# pot_controller_v1_0.net
KiCad netlist of a schematic drawn in EAGLE
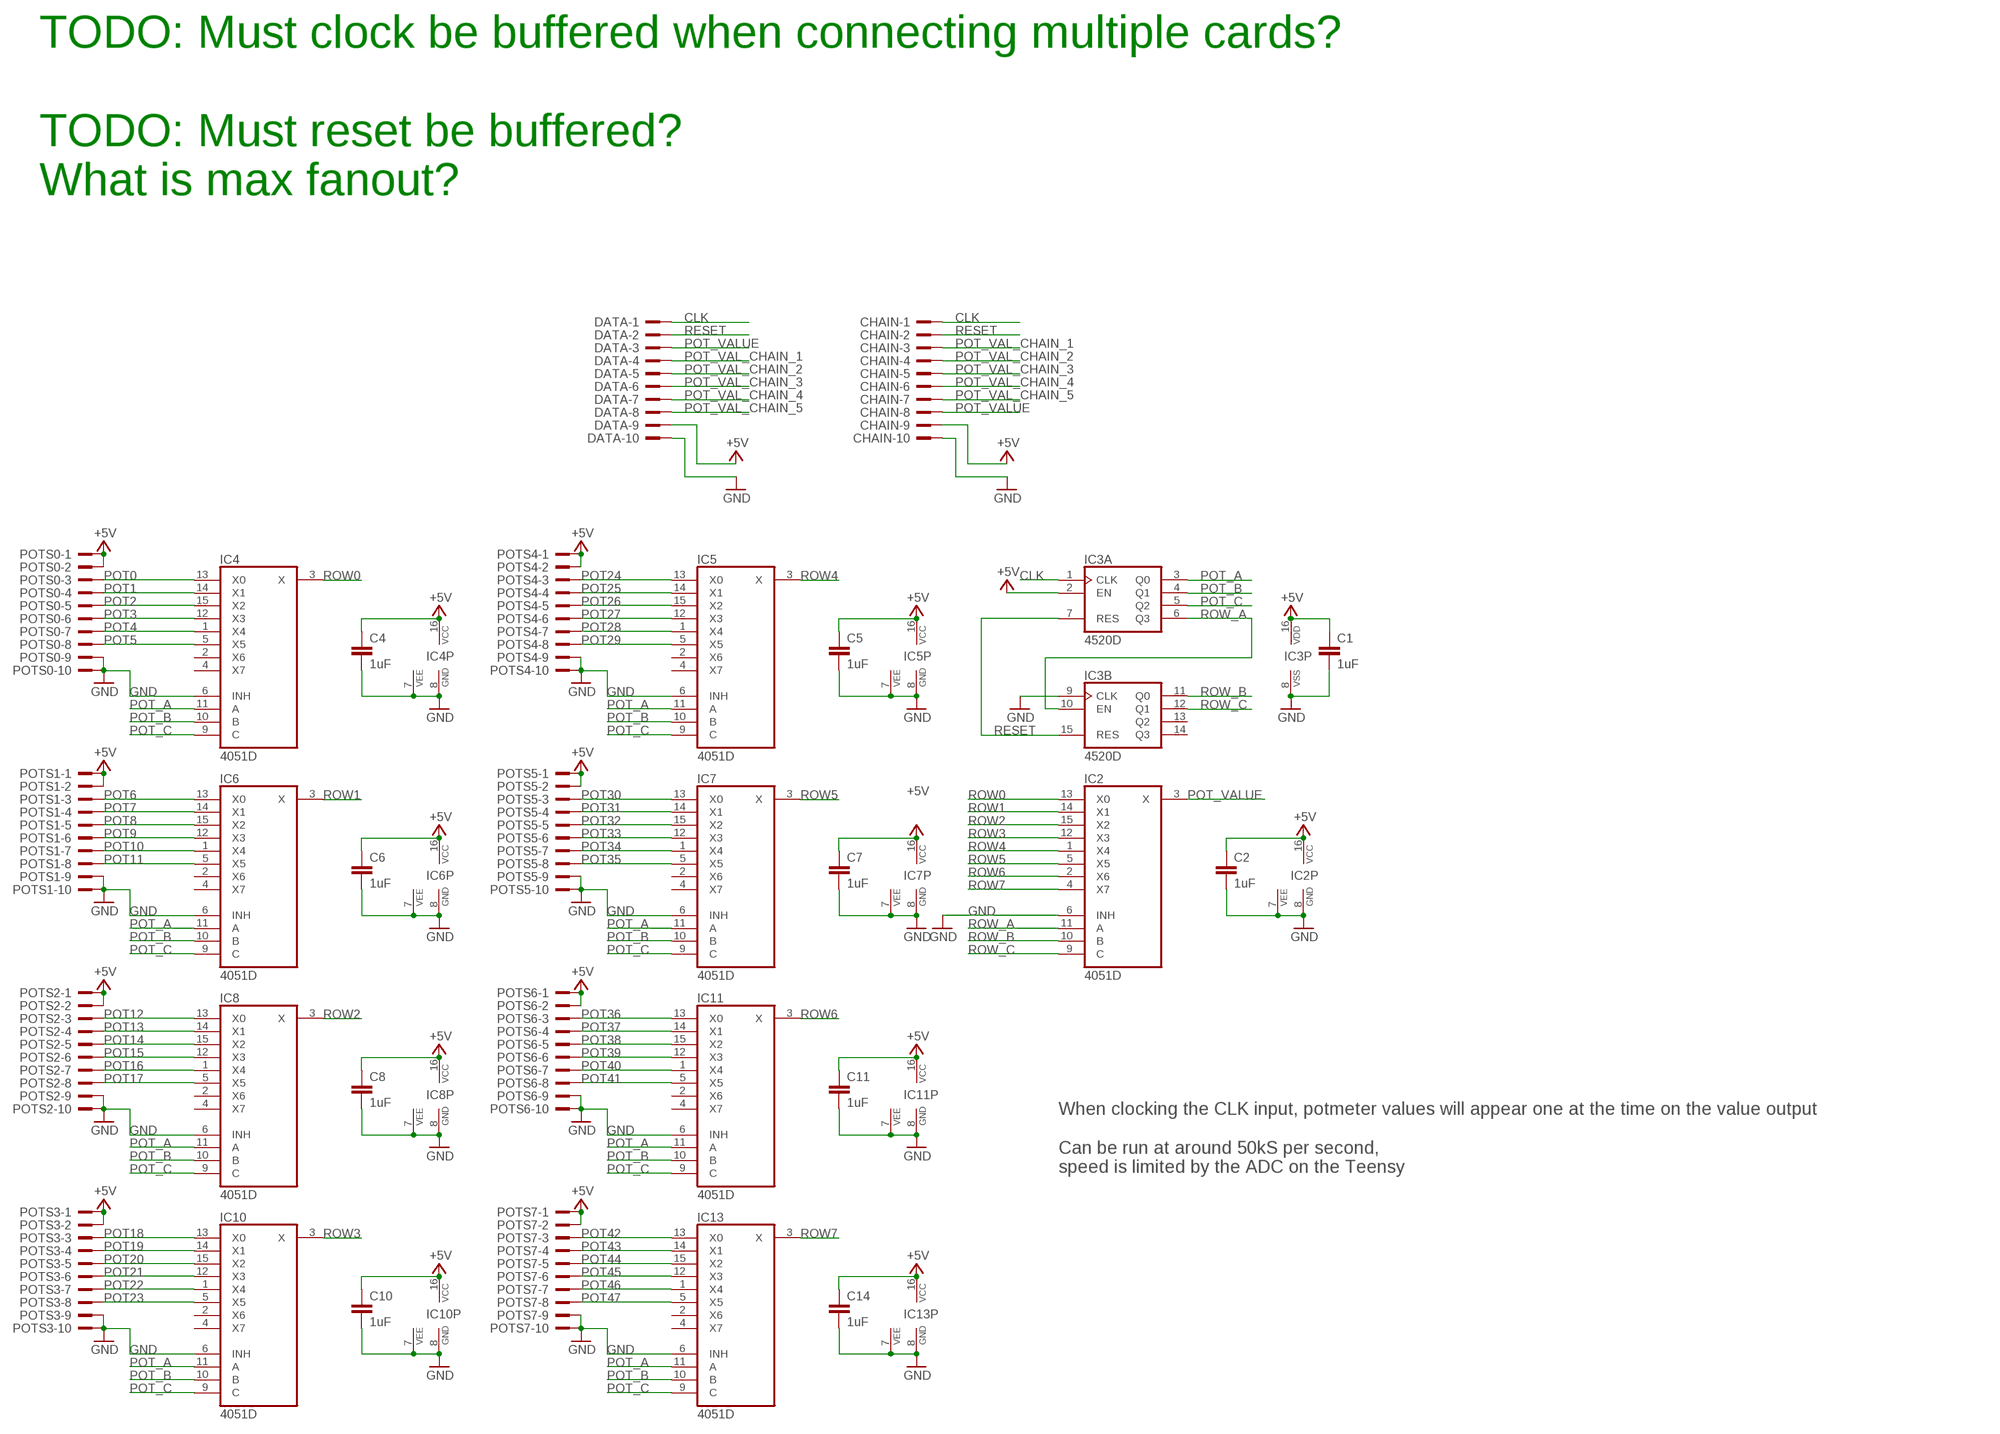
[diagram p0: schematic, sheet 1]

(export (version "E")
  (design (tool "Eeschema 10.0.6"))
  (components
    (comp (ref "C1")
      (value "1uF")
      (footprint "eagle-import:C0603-J")
      (libsource (lib "eagle-import") (part "C-EU-J0603"))
    )
    (comp (ref "C2")
      (value "1uF")
      (footprint "eagle-import:C0603-J")
      (libsource (lib "eagle-import") (part "C-EU-J0603"))
    )
    (comp (ref "C4")
      (value "1uF")
      (footprint "eagle-import:C0603-J")
      (libsource (lib "eagle-import") (part "C-EU-J0603"))
    )
    (comp (ref "C5")
      (value "1uF")
      (footprint "eagle-import:C0603-J")
      (libsource (lib "eagle-import") (part "C-EU-J0603"))
    )
    (comp (ref "C6")
      (value "1uF")
      (footprint "eagle-import:C0603-J")
      (libsource (lib "eagle-import") (part "C-EU-J0603"))
    )
    (comp (ref "C7")
      (value "1uF")
      (footprint "eagle-import:C0603-J")
      (libsource (lib "eagle-import") (part "C-EU-J0603"))
    )
    (comp (ref "C8")
      (value "1uF")
      (footprint "eagle-import:C0603-J")
      (libsource (lib "eagle-import") (part "C-EU-J0603"))
    )
    (comp (ref "C10")
      (value "1uF")
      (footprint "eagle-import:C0603-J")
      (libsource (lib "eagle-import") (part "C-EU-J0603"))
    )
    (comp (ref "C11")
      (value "1uF")
      (footprint "eagle-import:C0603-J")
      (libsource (lib "eagle-import") (part "C-EU-J0603"))
    )
    (comp (ref "C14")
      (value "1uF")
      (footprint "eagle-import:C0603-J")
      (libsource (lib "eagle-import") (part "C-EU-J0603"))
    )
    (comp (ref "CHAIN")
      (value "CONN-IDC-10PS")
      (footprint "eagle-import:CONN-IDC10P-S")
      (libsource (lib "eagle-import") (part "CONN-IDC-10PS"))
    )
    (comp (ref "DATA")
      (value "CONN-IDC-10PS")
      (footprint "eagle-import:CONN-IDC10P-S")
      (libsource (lib "eagle-import") (part "CONN-IDC-10PS"))
    )
    (comp (ref "IC2")
      (value "4051D")
      (footprint "eagle-import:SO16")
      (libsource (lib "eagle-import") (part "4051D"))
    )
    (comp (ref "IC3")
      (value "4520D")
      (footprint "eagle-import:SO16")
      (libsource (lib "eagle-import") (part "4520D"))
    )
    (comp (ref "IC4")
      (value "4051D")
      (footprint "eagle-import:SO16")
      (libsource (lib "eagle-import") (part "4051D"))
    )
    (comp (ref "IC5")
      (value "4051D")
      (footprint "eagle-import:SO16")
      (libsource (lib "eagle-import") (part "4051D"))
    )
    (comp (ref "IC6")
      (value "4051D")
      (footprint "eagle-import:SO16")
      (libsource (lib "eagle-import") (part "4051D"))
    )
    (comp (ref "IC7")
      (value "4051D")
      (footprint "eagle-import:SO16")
      (libsource (lib "eagle-import") (part "4051D"))
    )
    (comp (ref "IC8")
      (value "4051D")
      (footprint "eagle-import:SO16")
      (libsource (lib "eagle-import") (part "4051D"))
    )
    (comp (ref "IC10")
      (value "4051D")
      (footprint "eagle-import:SO16")
      (libsource (lib "eagle-import") (part "4051D"))
    )
    (comp (ref "IC11")
      (value "4051D")
      (footprint "eagle-import:SO16")
      (libsource (lib "eagle-import") (part "4051D"))
    )
    (comp (ref "IC13")
      (value "4051D")
      (footprint "eagle-import:SO16")
      (libsource (lib "eagle-import") (part "4051D"))
    )
    (comp (ref "POTS0")
      (value "CONN-IDC-10PS")
      (footprint "eagle-import:CONN-IDC10P-S")
      (libsource (lib "eagle-import") (part "CONN-IDC-10PS"))
    )
    (comp (ref "POTS1")
      (value "CONN-IDC-10PS")
      (footprint "eagle-import:CONN-IDC10P-S")
      (libsource (lib "eagle-import") (part "CONN-IDC-10PS"))
    )
    (comp (ref "POTS2")
      (value "CONN-IDC-10PS")
      (footprint "eagle-import:CONN-IDC10P-S")
      (libsource (lib "eagle-import") (part "CONN-IDC-10PS"))
    )
    (comp (ref "POTS3")
      (value "CONN-IDC-10PS")
      (footprint "eagle-import:CONN-IDC10P-S")
      (libsource (lib "eagle-import") (part "CONN-IDC-10PS"))
    )
    (comp (ref "POTS4")
      (value "CONN-IDC-10PS")
      (footprint "eagle-import:CONN-IDC10P-S")
      (libsource (lib "eagle-import") (part "CONN-IDC-10PS"))
    )
    (comp (ref "POTS5")
      (value "CONN-IDC-10PS")
      (footprint "eagle-import:CONN-IDC10P-S")
      (libsource (lib "eagle-import") (part "CONN-IDC-10PS"))
    )
    (comp (ref "POTS6")
      (value "CONN-IDC-10PS")
      (footprint "eagle-import:CONN-IDC10P-S")
      (libsource (lib "eagle-import") (part "CONN-IDC-10PS"))
    )
    (comp (ref "POTS7")
      (value "CONN-IDC-10PS")
      (footprint "eagle-import:CONN-IDC10P-S")
      (libsource (lib "eagle-import") (part "CONN-IDC-10PS"))
    )
  )
  (nets
    (net (code "1") (name "+5V") (class "Default")
      (node (ref "C1") (pin "1") (pinfunction "1_1") (pintype "passive"))
      (node (ref "C10") (pin "1") (pinfunction "1_1") (pintype "passive"))
      (node (ref "C11") (pin "1") (pinfunction "1_1") (pintype "passive"))
      (node (ref "C14") (pin "1") (pinfunction "1_1") (pintype "passive"))
      (node (ref "C2") (pin "1") (pinfunction "1_1") (pintype "passive"))
      (node (ref "C4") (pin "1") (pinfunction "1_1") (pintype "passive"))
      (node (ref "C5") (pin "1") (pinfunction "1_1") (pintype "passive"))
      (node (ref "C6") (pin "1") (pinfunction "1_1") (pintype "passive"))
      (node (ref "C7") (pin "1") (pinfunction "1_1") (pintype "passive"))
      (node (ref "C8") (pin "1") (pinfunction "1_1") (pintype "passive"))
      (node (ref "CHAIN") (pin "9") (pinfunction "KL_9") (pintype "passive"))
      (node (ref "DATA") (pin "9") (pinfunction "KL_9") (pintype "passive"))
      (node (ref "IC10") (pin "16") (pinfunction "VCC_16") (pintype "power_in"))
      (node (ref "IC11") (pin "16") (pinfunction "VCC_16") (pintype "power_in"))
      (node (ref "IC13") (pin "16") (pinfunction "VCC_16") (pintype "power_in"))
      (node (ref "IC2") (pin "16") (pinfunction "VCC_16") (pintype "power_in"))
      (node (ref "IC3") (pin "16") (pinfunction "VDD_16") (pintype "power_in"))
      (node (ref "IC3") (pin "2") (pinfunction "EN_2") (pintype "input"))
      (node (ref "IC4") (pin "16") (pinfunction "VCC_16") (pintype "power_in"))
      (node (ref "IC5") (pin "16") (pinfunction "VCC_16") (pintype "power_in"))
      (node (ref "IC6") (pin "16") (pinfunction "VCC_16") (pintype "power_in"))
      (node (ref "IC7") (pin "16") (pinfunction "VCC_16") (pintype "power_in"))
      (node (ref "IC8") (pin "16") (pinfunction "VCC_16") (pintype "power_in"))
      (node (ref "POTS0") (pin "1") (pinfunction "KL_1") (pintype "passive"))
      (node (ref "POTS0") (pin "2") (pinfunction "KL_2") (pintype "passive"))
      (node (ref "POTS1") (pin "1") (pinfunction "KL_1") (pintype "passive"))
      (node (ref "POTS1") (pin "2") (pinfunction "KL_2") (pintype "passive"))
      (node (ref "POTS2") (pin "1") (pinfunction "KL_1") (pintype "passive"))
      (node (ref "POTS2") (pin "2") (pinfunction "KL_2") (pintype "passive"))
      (node (ref "POTS3") (pin "1") (pinfunction "KL_1") (pintype "passive"))
      (node (ref "POTS3") (pin "2") (pinfunction "KL_2") (pintype "passive"))
      (node (ref "POTS4") (pin "1") (pinfunction "KL_1") (pintype "passive"))
      (node (ref "POTS4") (pin "2") (pinfunction "KL_2") (pintype "passive"))
      (node (ref "POTS5") (pin "1") (pinfunction "KL_1") (pintype "passive"))
      (node (ref "POTS5") (pin "2") (pinfunction "KL_2") (pintype "passive"))
      (node (ref "POTS6") (pin "1") (pinfunction "KL_1") (pintype "passive"))
      (node (ref "POTS6") (pin "2") (pinfunction "KL_2") (pintype "passive"))
      (node (ref "POTS7") (pin "1") (pinfunction "KL_1") (pintype "passive"))
      (node (ref "POTS7") (pin "2") (pinfunction "KL_2") (pintype "passive"))
    )
    (net (code "2") (name "/CLK") (class "Default")
      (node (ref "CHAIN") (pin "1") (pinfunction "KL_1") (pintype "passive"))
      (node (ref "DATA") (pin "1") (pinfunction "KL_1") (pintype "passive"))
      (node (ref "IC3") (pin "1") (pinfunction "CLK_1") (pintype "input"))
    )
    (net (code "3") (name "/POT0") (class "Default")
      (node (ref "IC4") (pin "13") (pinfunction "X0_13") (pintype "bidirectional"))
      (node (ref "POTS0") (pin "3") (pinfunction "KL_3") (pintype "passive"))
    )
    (net (code "4") (name "/POT1") (class "Default")
      (node (ref "IC4") (pin "14") (pinfunction "X1_14") (pintype "bidirectional"))
      (node (ref "POTS0") (pin "4") (pinfunction "KL_4") (pintype "passive"))
    )
    (net (code "5") (name "/POT2") (class "Default")
      (node (ref "IC4") (pin "15") (pinfunction "X2_15") (pintype "bidirectional"))
      (node (ref "POTS0") (pin "5") (pinfunction "KL_5") (pintype "passive"))
    )
    (net (code "6") (name "/POT3") (class "Default")
      (node (ref "IC4") (pin "12") (pinfunction "X3_12") (pintype "bidirectional"))
      (node (ref "POTS0") (pin "6") (pinfunction "KL_6") (pintype "passive"))
    )
    (net (code "7") (name "/POT4") (class "Default")
      (node (ref "IC4") (pin "1") (pinfunction "X4_1") (pintype "bidirectional"))
      (node (ref "POTS0") (pin "7") (pinfunction "KL_7") (pintype "passive"))
    )
    (net (code "8") (name "/POT5") (class "Default")
      (node (ref "IC4") (pin "5") (pinfunction "X5_5") (pintype "bidirectional"))
      (node (ref "POTS0") (pin "8") (pinfunction "KL_8") (pintype "passive"))
    )
    (net (code "9") (name "/POT6") (class "Default")
      (node (ref "IC6") (pin "13") (pinfunction "X0_13") (pintype "bidirectional"))
      (node (ref "POTS1") (pin "3") (pinfunction "KL_3") (pintype "passive"))
    )
    (net (code "10") (name "/POT7") (class "Default")
      (node (ref "IC6") (pin "14") (pinfunction "X1_14") (pintype "bidirectional"))
      (node (ref "POTS1") (pin "4") (pinfunction "KL_4") (pintype "passive"))
    )
    (net (code "11") (name "/POT8") (class "Default")
      (node (ref "IC6") (pin "15") (pinfunction "X2_15") (pintype "bidirectional"))
      (node (ref "POTS1") (pin "5") (pinfunction "KL_5") (pintype "passive"))
    )
    (net (code "12") (name "/POT9") (class "Default")
      (node (ref "IC6") (pin "12") (pinfunction "X3_12") (pintype "bidirectional"))
      (node (ref "POTS1") (pin "6") (pinfunction "KL_6") (pintype "passive"))
    )
    (net (code "13") (name "/POT10") (class "Default")
      (node (ref "IC6") (pin "1") (pinfunction "X4_1") (pintype "bidirectional"))
      (node (ref "POTS1") (pin "7") (pinfunction "KL_7") (pintype "passive"))
    )
    (net (code "14") (name "/POT11") (class "Default")
      (node (ref "IC6") (pin "5") (pinfunction "X5_5") (pintype "bidirectional"))
      (node (ref "POTS1") (pin "8") (pinfunction "KL_8") (pintype "passive"))
    )
    (net (code "15") (name "/POT12") (class "Default")
      (node (ref "IC8") (pin "13") (pinfunction "X0_13") (pintype "bidirectional"))
      (node (ref "POTS2") (pin "3") (pinfunction "KL_3") (pintype "passive"))
    )
    (net (code "16") (name "/POT13") (class "Default")
      (node (ref "IC8") (pin "14") (pinfunction "X1_14") (pintype "bidirectional"))
      (node (ref "POTS2") (pin "4") (pinfunction "KL_4") (pintype "passive"))
    )
    (net (code "17") (name "/POT14") (class "Default")
      (node (ref "IC8") (pin "15") (pinfunction "X2_15") (pintype "bidirectional"))
      (node (ref "POTS2") (pin "5") (pinfunction "KL_5") (pintype "passive"))
    )
    (net (code "18") (name "/POT15") (class "Default")
      (node (ref "IC8") (pin "12") (pinfunction "X3_12") (pintype "bidirectional"))
      (node (ref "POTS2") (pin "6") (pinfunction "KL_6") (pintype "passive"))
    )
    (net (code "19") (name "/POT16") (class "Default")
      (node (ref "IC8") (pin "1") (pinfunction "X4_1") (pintype "bidirectional"))
      (node (ref "POTS2") (pin "7") (pinfunction "KL_7") (pintype "passive"))
    )
    (net (code "20") (name "/POT17") (class "Default")
      (node (ref "IC8") (pin "5") (pinfunction "X5_5") (pintype "bidirectional"))
      (node (ref "POTS2") (pin "8") (pinfunction "KL_8") (pintype "passive"))
    )
    (net (code "21") (name "/POT18") (class "Default")
      (node (ref "IC10") (pin "13") (pinfunction "X0_13") (pintype "bidirectional"))
      (node (ref "POTS3") (pin "3") (pinfunction "KL_3") (pintype "passive"))
    )
    (net (code "22") (name "/POT19") (class "Default")
      (node (ref "IC10") (pin "14") (pinfunction "X1_14") (pintype "bidirectional"))
      (node (ref "POTS3") (pin "4") (pinfunction "KL_4") (pintype "passive"))
    )
    (net (code "23") (name "/POT20") (class "Default")
      (node (ref "IC10") (pin "15") (pinfunction "X2_15") (pintype "bidirectional"))
      (node (ref "POTS3") (pin "5") (pinfunction "KL_5") (pintype "passive"))
    )
    (net (code "24") (name "/POT21") (class "Default")
      (node (ref "IC10") (pin "12") (pinfunction "X3_12") (pintype "bidirectional"))
      (node (ref "POTS3") (pin "6") (pinfunction "KL_6") (pintype "passive"))
    )
    (net (code "25") (name "/POT22") (class "Default")
      (node (ref "IC10") (pin "1") (pinfunction "X4_1") (pintype "bidirectional"))
      (node (ref "POTS3") (pin "7") (pinfunction "KL_7") (pintype "passive"))
    )
    (net (code "26") (name "/POT23") (class "Default")
      (node (ref "IC10") (pin "5") (pinfunction "X5_5") (pintype "bidirectional"))
      (node (ref "POTS3") (pin "8") (pinfunction "KL_8") (pintype "passive"))
    )
    (net (code "27") (name "/POT24") (class "Default")
      (node (ref "IC5") (pin "13") (pinfunction "X0_13") (pintype "bidirectional"))
      (node (ref "POTS4") (pin "3") (pinfunction "KL_3") (pintype "passive"))
    )
    (net (code "28") (name "/POT25") (class "Default")
      (node (ref "IC5") (pin "14") (pinfunction "X1_14") (pintype "bidirectional"))
      (node (ref "POTS4") (pin "4") (pinfunction "KL_4") (pintype "passive"))
    )
    (net (code "29") (name "/POT26") (class "Default")
      (node (ref "IC5") (pin "15") (pinfunction "X2_15") (pintype "bidirectional"))
      (node (ref "POTS4") (pin "5") (pinfunction "KL_5") (pintype "passive"))
    )
    (net (code "30") (name "/POT27") (class "Default")
      (node (ref "IC5") (pin "12") (pinfunction "X3_12") (pintype "bidirectional"))
      (node (ref "POTS4") (pin "6") (pinfunction "KL_6") (pintype "passive"))
    )
    (net (code "31") (name "/POT28") (class "Default")
      (node (ref "IC5") (pin "1") (pinfunction "X4_1") (pintype "bidirectional"))
      (node (ref "POTS4") (pin "7") (pinfunction "KL_7") (pintype "passive"))
    )
    (net (code "32") (name "/POT29") (class "Default")
      (node (ref "IC5") (pin "5") (pinfunction "X5_5") (pintype "bidirectional"))
      (node (ref "POTS4") (pin "8") (pinfunction "KL_8") (pintype "passive"))
    )
    (net (code "33") (name "/POT30") (class "Default")
      (node (ref "IC7") (pin "13") (pinfunction "X0_13") (pintype "bidirectional"))
      (node (ref "POTS5") (pin "3") (pinfunction "KL_3") (pintype "passive"))
    )
    (net (code "34") (name "/POT31") (class "Default")
      (node (ref "IC7") (pin "14") (pinfunction "X1_14") (pintype "bidirectional"))
      (node (ref "POTS5") (pin "4") (pinfunction "KL_4") (pintype "passive"))
    )
    (net (code "35") (name "/POT32") (class "Default")
      (node (ref "IC7") (pin "15") (pinfunction "X2_15") (pintype "bidirectional"))
      (node (ref "POTS5") (pin "5") (pinfunction "KL_5") (pintype "passive"))
    )
    (net (code "36") (name "/POT33") (class "Default")
      (node (ref "IC7") (pin "12") (pinfunction "X3_12") (pintype "bidirectional"))
      (node (ref "POTS5") (pin "6") (pinfunction "KL_6") (pintype "passive"))
    )
    (net (code "37") (name "/POT34") (class "Default")
      (node (ref "IC7") (pin "1") (pinfunction "X4_1") (pintype "bidirectional"))
      (node (ref "POTS5") (pin "7") (pinfunction "KL_7") (pintype "passive"))
    )
    (net (code "38") (name "/POT35") (class "Default")
      (node (ref "IC7") (pin "5") (pinfunction "X5_5") (pintype "bidirectional"))
      (node (ref "POTS5") (pin "8") (pinfunction "KL_8") (pintype "passive"))
    )
    (net (code "39") (name "/POT36") (class "Default")
      (node (ref "IC11") (pin "13") (pinfunction "X0_13") (pintype "bidirectional"))
      (node (ref "POTS6") (pin "3") (pinfunction "KL_3") (pintype "passive"))
    )
    (net (code "40") (name "/POT37") (class "Default")
      (node (ref "IC11") (pin "14") (pinfunction "X1_14") (pintype "bidirectional"))
      (node (ref "POTS6") (pin "4") (pinfunction "KL_4") (pintype "passive"))
    )
    (net (code "41") (name "/POT38") (class "Default")
      (node (ref "IC11") (pin "15") (pinfunction "X2_15") (pintype "bidirectional"))
      (node (ref "POTS6") (pin "5") (pinfunction "KL_5") (pintype "passive"))
    )
    (net (code "42") (name "/POT39") (class "Default")
      (node (ref "IC11") (pin "12") (pinfunction "X3_12") (pintype "bidirectional"))
      (node (ref "POTS6") (pin "6") (pinfunction "KL_6") (pintype "passive"))
    )
    (net (code "43") (name "/POT40") (class "Default")
      (node (ref "IC11") (pin "1") (pinfunction "X4_1") (pintype "bidirectional"))
      (node (ref "POTS6") (pin "7") (pinfunction "KL_7") (pintype "passive"))
    )
    (net (code "44") (name "/POT41") (class "Default")
      (node (ref "IC11") (pin "5") (pinfunction "X5_5") (pintype "bidirectional"))
      (node (ref "POTS6") (pin "8") (pinfunction "KL_8") (pintype "passive"))
    )
    (net (code "45") (name "/POT42") (class "Default")
      (node (ref "IC13") (pin "13") (pinfunction "X0_13") (pintype "bidirectional"))
      (node (ref "POTS7") (pin "3") (pinfunction "KL_3") (pintype "passive"))
    )
    (net (code "46") (name "/POT43") (class "Default")
      (node (ref "IC13") (pin "14") (pinfunction "X1_14") (pintype "bidirectional"))
      (node (ref "POTS7") (pin "4") (pinfunction "KL_4") (pintype "passive"))
    )
    (net (code "47") (name "/POT44") (class "Default")
      (node (ref "IC13") (pin "15") (pinfunction "X2_15") (pintype "bidirectional"))
      (node (ref "POTS7") (pin "5") (pinfunction "KL_5") (pintype "passive"))
    )
    (net (code "48") (name "/POT45") (class "Default")
      (node (ref "IC13") (pin "12") (pinfunction "X3_12") (pintype "bidirectional"))
      (node (ref "POTS7") (pin "6") (pinfunction "KL_6") (pintype "passive"))
    )
    (net (code "49") (name "/POT46") (class "Default")
      (node (ref "IC13") (pin "1") (pinfunction "X4_1") (pintype "bidirectional"))
      (node (ref "POTS7") (pin "7") (pinfunction "KL_7") (pintype "passive"))
    )
    (net (code "50") (name "/POT47") (class "Default")
      (node (ref "IC13") (pin "5") (pinfunction "X5_5") (pintype "bidirectional"))
      (node (ref "POTS7") (pin "8") (pinfunction "KL_8") (pintype "passive"))
    )
    (net (code "51") (name "/POT_A") (class "Default")
      (node (ref "IC10") (pin "11") (pinfunction "A_11") (pintype "input"))
      (node (ref "IC11") (pin "11") (pinfunction "A_11") (pintype "input"))
      (node (ref "IC13") (pin "11") (pinfunction "A_11") (pintype "input"))
      (node (ref "IC3") (pin "3") (pinfunction "Q0_3") (pintype "output"))
      (node (ref "IC4") (pin "11") (pinfunction "A_11") (pintype "input"))
      (node (ref "IC5") (pin "11") (pinfunction "A_11") (pintype "input"))
      (node (ref "IC6") (pin "11") (pinfunction "A_11") (pintype "input"))
      (node (ref "IC7") (pin "11") (pinfunction "A_11") (pintype "input"))
      (node (ref "IC8") (pin "11") (pinfunction "A_11") (pintype "input"))
    )
    (net (code "52") (name "/POT_B") (class "Default")
      (node (ref "IC10") (pin "10") (pinfunction "B_10") (pintype "input"))
      (node (ref "IC11") (pin "10") (pinfunction "B_10") (pintype "input"))
      (node (ref "IC13") (pin "10") (pinfunction "B_10") (pintype "input"))
      (node (ref "IC3") (pin "4") (pinfunction "Q1_4") (pintype "output"))
      (node (ref "IC4") (pin "10") (pinfunction "B_10") (pintype "input"))
      (node (ref "IC5") (pin "10") (pinfunction "B_10") (pintype "input"))
      (node (ref "IC6") (pin "10") (pinfunction "B_10") (pintype "input"))
      (node (ref "IC7") (pin "10") (pinfunction "B_10") (pintype "input"))
      (node (ref "IC8") (pin "10") (pinfunction "B_10") (pintype "input"))
    )
    (net (code "53") (name "/POT_C") (class "Default")
      (node (ref "IC10") (pin "9") (pinfunction "C_9") (pintype "input"))
      (node (ref "IC11") (pin "9") (pinfunction "C_9") (pintype "input"))
      (node (ref "IC13") (pin "9") (pinfunction "C_9") (pintype "input"))
      (node (ref "IC3") (pin "5") (pinfunction "Q2_5") (pintype "output"))
      (node (ref "IC4") (pin "9") (pinfunction "C_9") (pintype "input"))
      (node (ref "IC5") (pin "9") (pinfunction "C_9") (pintype "input"))
      (node (ref "IC6") (pin "9") (pinfunction "C_9") (pintype "input"))
      (node (ref "IC7") (pin "9") (pinfunction "C_9") (pintype "input"))
      (node (ref "IC8") (pin "9") (pinfunction "C_9") (pintype "input"))
    )
    (net (code "54") (name "/POT_VALUE") (class "Default")
      (node (ref "CHAIN") (pin "8") (pinfunction "KL_8") (pintype "passive"))
      (node (ref "DATA") (pin "3") (pinfunction "KL_3") (pintype "passive"))
      (node (ref "IC2") (pin "3") (pinfunction "X_3") (pintype "bidirectional"))
    )
    (net (code "55") (name "/POT_VAL_CHAIN_1") (class "Default")
      (node (ref "CHAIN") (pin "3") (pinfunction "KL_3") (pintype "passive"))
      (node (ref "DATA") (pin "4") (pinfunction "KL_4") (pintype "passive"))
    )
    (net (code "56") (name "/POT_VAL_CHAIN_2") (class "Default")
      (node (ref "CHAIN") (pin "4") (pinfunction "KL_4") (pintype "passive"))
      (node (ref "DATA") (pin "5") (pinfunction "KL_5") (pintype "passive"))
    )
    (net (code "57") (name "/POT_VAL_CHAIN_3") (class "Default")
      (node (ref "CHAIN") (pin "5") (pinfunction "KL_5") (pintype "passive"))
      (node (ref "DATA") (pin "6") (pinfunction "KL_6") (pintype "passive"))
    )
    (net (code "58") (name "/POT_VAL_CHAIN_4") (class "Default")
      (node (ref "CHAIN") (pin "6") (pinfunction "KL_6") (pintype "passive"))
      (node (ref "DATA") (pin "7") (pinfunction "KL_7") (pintype "passive"))
    )
    (net (code "59") (name "/POT_VAL_CHAIN_5") (class "Default")
      (node (ref "CHAIN") (pin "7") (pinfunction "KL_7") (pintype "passive"))
      (node (ref "DATA") (pin "8") (pinfunction "KL_8") (pintype "passive"))
    )
    (net (code "60") (name "/RESET") (class "Default")
      (node (ref "CHAIN") (pin "2") (pinfunction "KL_2") (pintype "passive"))
      (node (ref "DATA") (pin "2") (pinfunction "KL_2") (pintype "passive"))
      (node (ref "IC3") (pin "15") (pinfunction "RES_15") (pintype "input"))
      (node (ref "IC3") (pin "7") (pinfunction "RES_7") (pintype "input"))
    )
    (net (code "61") (name "/ROW0") (class "Default")
      (node (ref "IC2") (pin "13") (pinfunction "X0_13") (pintype "bidirectional"))
      (node (ref "IC4") (pin "3") (pinfunction "X_3") (pintype "bidirectional"))
    )
    (net (code "62") (name "/ROW1") (class "Default")
      (node (ref "IC2") (pin "14") (pinfunction "X1_14") (pintype "bidirectional"))
      (node (ref "IC6") (pin "3") (pinfunction "X_3") (pintype "bidirectional"))
    )
    (net (code "63") (name "/ROW2") (class "Default")
      (node (ref "IC2") (pin "15") (pinfunction "X2_15") (pintype "bidirectional"))
      (node (ref "IC8") (pin "3") (pinfunction "X_3") (pintype "bidirectional"))
    )
    (net (code "64") (name "/ROW3") (class "Default")
      (node (ref "IC10") (pin "3") (pinfunction "X_3") (pintype "bidirectional"))
      (node (ref "IC2") (pin "12") (pinfunction "X3_12") (pintype "bidirectional"))
    )
    (net (code "65") (name "/ROW4") (class "Default")
      (node (ref "IC2") (pin "1") (pinfunction "X4_1") (pintype "bidirectional"))
      (node (ref "IC5") (pin "3") (pinfunction "X_3") (pintype "bidirectional"))
    )
    (net (code "66") (name "/ROW5") (class "Default")
      (node (ref "IC2") (pin "5") (pinfunction "X5_5") (pintype "bidirectional"))
      (node (ref "IC7") (pin "3") (pinfunction "X_3") (pintype "bidirectional"))
    )
    (net (code "67") (name "/ROW6") (class "Default")
      (node (ref "IC11") (pin "3") (pinfunction "X_3") (pintype "bidirectional"))
      (node (ref "IC2") (pin "2") (pinfunction "X6_2") (pintype "bidirectional"))
    )
    (net (code "68") (name "/ROW7") (class "Default")
      (node (ref "IC13") (pin "3") (pinfunction "X_3") (pintype "bidirectional"))
      (node (ref "IC2") (pin "4") (pinfunction "X7_4") (pintype "bidirectional"))
    )
    (net (code "69") (name "/ROW_A") (class "Default")
      (node (ref "IC2") (pin "11") (pinfunction "A_11") (pintype "input"))
      (node (ref "IC3") (pin "10") (pinfunction "EN_10") (pintype "input"))
      (node (ref "IC3") (pin "6") (pinfunction "Q3_6") (pintype "output"))
    )
    (net (code "70") (name "/ROW_B") (class "Default")
      (node (ref "IC2") (pin "10") (pinfunction "B_10") (pintype "input"))
      (node (ref "IC3") (pin "11") (pinfunction "Q0_11") (pintype "output"))
    )
    (net (code "71") (name "/ROW_C") (class "Default")
      (node (ref "IC2") (pin "9") (pinfunction "C_9") (pintype "input"))
      (node (ref "IC3") (pin "12") (pinfunction "Q1_12") (pintype "output"))
    )
    (net (code "72") (name "GND") (class "Default")
      (node (ref "C1") (pin "2") (pinfunction "2_2") (pintype "passive"))
      (node (ref "C10") (pin "2") (pinfunction "2_2") (pintype "passive"))
      (node (ref "C11") (pin "2") (pinfunction "2_2") (pintype "passive"))
      (node (ref "C14") (pin "2") (pinfunction "2_2") (pintype "passive"))
      (node (ref "C2") (pin "2") (pinfunction "2_2") (pintype "passive"))
      (node (ref "C4") (pin "2") (pinfunction "2_2") (pintype "passive"))
      (node (ref "C5") (pin "2") (pinfunction "2_2") (pintype "passive"))
      (node (ref "C6") (pin "2") (pinfunction "2_2") (pintype "passive"))
      (node (ref "C7") (pin "2") (pinfunction "2_2") (pintype "passive"))
      (node (ref "C8") (pin "2") (pinfunction "2_2") (pintype "passive"))
      (node (ref "CHAIN") (pin "10") (pinfunction "KL_10") (pintype "passive"))
      (node (ref "DATA") (pin "10") (pinfunction "KL_10") (pintype "passive"))
      (node (ref "IC10") (pin "6") (pinfunction "INH_6") (pintype "input"))
      (node (ref "IC10") (pin "7") (pinfunction "VEE_7") (pintype "power_in"))
      (node (ref "IC10") (pin "8") (pinfunction "GND_8") (pintype "power_in"))
      (node (ref "IC11") (pin "6") (pinfunction "INH_6") (pintype "input"))
      (node (ref "IC11") (pin "7") (pinfunction "VEE_7") (pintype "power_in"))
      (node (ref "IC11") (pin "8") (pinfunction "GND_8") (pintype "power_in"))
      (node (ref "IC13") (pin "6") (pinfunction "INH_6") (pintype "input"))
      (node (ref "IC13") (pin "7") (pinfunction "VEE_7") (pintype "power_in"))
      (node (ref "IC13") (pin "8") (pinfunction "GND_8") (pintype "power_in"))
      (node (ref "IC2") (pin "6") (pinfunction "INH_6") (pintype "input"))
      (node (ref "IC2") (pin "7") (pinfunction "VEE_7") (pintype "power_in"))
      (node (ref "IC2") (pin "8") (pinfunction "GND_8") (pintype "power_in"))
      (node (ref "IC3") (pin "8") (pinfunction "VSS_8") (pintype "power_in"))
      (node (ref "IC3") (pin "9") (pinfunction "CLK_9") (pintype "input"))
      (node (ref "IC4") (pin "6") (pinfunction "INH_6") (pintype "input"))
      (node (ref "IC4") (pin "7") (pinfunction "VEE_7") (pintype "power_in"))
      (node (ref "IC4") (pin "8") (pinfunction "GND_8") (pintype "power_in"))
      (node (ref "IC5") (pin "6") (pinfunction "INH_6") (pintype "input"))
      (node (ref "IC5") (pin "7") (pinfunction "VEE_7") (pintype "power_in"))
      (node (ref "IC5") (pin "8") (pinfunction "GND_8") (pintype "power_in"))
      (node (ref "IC6") (pin "6") (pinfunction "INH_6") (pintype "input"))
      (node (ref "IC6") (pin "7") (pinfunction "VEE_7") (pintype "power_in"))
      (node (ref "IC6") (pin "8") (pinfunction "GND_8") (pintype "power_in"))
      (node (ref "IC7") (pin "6") (pinfunction "INH_6") (pintype "input"))
      (node (ref "IC7") (pin "7") (pinfunction "VEE_7") (pintype "power_in"))
      (node (ref "IC7") (pin "8") (pinfunction "GND_8") (pintype "power_in"))
      (node (ref "IC8") (pin "6") (pinfunction "INH_6") (pintype "input"))
      (node (ref "IC8") (pin "7") (pinfunction "VEE_7") (pintype "power_in"))
      (node (ref "IC8") (pin "8") (pinfunction "GND_8") (pintype "power_in"))
      (node (ref "POTS0") (pin "10") (pinfunction "KL_10") (pintype "passive"))
      (node (ref "POTS0") (pin "9") (pinfunction "KL_9") (pintype "passive"))
      (node (ref "POTS1") (pin "10") (pinfunction "KL_10") (pintype "passive"))
      (node (ref "POTS1") (pin "9") (pinfunction "KL_9") (pintype "passive"))
      (node (ref "POTS2") (pin "10") (pinfunction "KL_10") (pintype "passive"))
      (node (ref "POTS2") (pin "9") (pinfunction "KL_9") (pintype "passive"))
      (node (ref "POTS3") (pin "10") (pinfunction "KL_10") (pintype "passive"))
      (node (ref "POTS3") (pin "9") (pinfunction "KL_9") (pintype "passive"))
      (node (ref "POTS4") (pin "10") (pinfunction "KL_10") (pintype "passive"))
      (node (ref "POTS4") (pin "9") (pinfunction "KL_9") (pintype "passive"))
      (node (ref "POTS5") (pin "10") (pinfunction "KL_10") (pintype "passive"))
      (node (ref "POTS5") (pin "9") (pinfunction "KL_9") (pintype "passive"))
      (node (ref "POTS6") (pin "10") (pinfunction "KL_10") (pintype "passive"))
      (node (ref "POTS6") (pin "9") (pinfunction "KL_9") (pintype "passive"))
      (node (ref "POTS7") (pin "10") (pinfunction "KL_10") (pintype "passive"))
      (node (ref "POTS7") (pin "9") (pinfunction "KL_9") (pintype "passive"))
    )
    (net (code "73") (name "unconnected-(IC3B-Q2-Pad13)") (class "Default")
      (node (ref "IC3") (pin "13") (pinfunction "Q2_13") (pintype "output"))
    )
    (net (code "74") (name "unconnected-(IC3B-Q3-Pad14)") (class "Default")
      (node (ref "IC3") (pin "14") (pinfunction "Q3_14") (pintype "output"))
    )
    (net (code "75") (name "unconnected-(IC4A-X6-Pad2)") (class "Default")
      (node (ref "IC4") (pin "2") (pinfunction "X6_2") (pintype "bidirectional"))
    )
    (net (code "76") (name "unconnected-(IC4A-X7-Pad4)") (class "Default")
      (node (ref "IC4") (pin "4") (pinfunction "X7_4") (pintype "bidirectional"))
    )
    (net (code "77") (name "unconnected-(IC5A-X6-Pad2)") (class "Default")
      (node (ref "IC5") (pin "2") (pinfunction "X6_2") (pintype "bidirectional"))
    )
    (net (code "78") (name "unconnected-(IC5A-X7-Pad4)") (class "Default")
      (node (ref "IC5") (pin "4") (pinfunction "X7_4") (pintype "bidirectional"))
    )
    (net (code "79") (name "unconnected-(IC6A-X6-Pad2)") (class "Default")
      (node (ref "IC6") (pin "2") (pinfunction "X6_2") (pintype "bidirectional"))
    )
    (net (code "80") (name "unconnected-(IC6A-X7-Pad4)") (class "Default")
      (node (ref "IC6") (pin "4") (pinfunction "X7_4") (pintype "bidirectional"))
    )
    (net (code "81") (name "unconnected-(IC7A-X6-Pad2)") (class "Default")
      (node (ref "IC7") (pin "2") (pinfunction "X6_2") (pintype "bidirectional"))
    )
    (net (code "82") (name "unconnected-(IC7A-X7-Pad4)") (class "Default")
      (node (ref "IC7") (pin "4") (pinfunction "X7_4") (pintype "bidirectional"))
    )
    (net (code "83") (name "unconnected-(IC8A-X6-Pad2)") (class "Default")
      (node (ref "IC8") (pin "2") (pinfunction "X6_2") (pintype "bidirectional"))
    )
    (net (code "84") (name "unconnected-(IC8A-X7-Pad4)") (class "Default")
      (node (ref "IC8") (pin "4") (pinfunction "X7_4") (pintype "bidirectional"))
    )
    (net (code "85") (name "unconnected-(IC10A-X6-Pad2)") (class "Default")
      (node (ref "IC10") (pin "2") (pinfunction "X6_2") (pintype "bidirectional"))
    )
    (net (code "86") (name "unconnected-(IC10A-X7-Pad4)") (class "Default")
      (node (ref "IC10") (pin "4") (pinfunction "X7_4") (pintype "bidirectional"))
    )
    (net (code "87") (name "unconnected-(IC11A-X6-Pad2)") (class "Default")
      (node (ref "IC11") (pin "2") (pinfunction "X6_2") (pintype "bidirectional"))
    )
    (net (code "88") (name "unconnected-(IC11A-X7-Pad4)") (class "Default")
      (node (ref "IC11") (pin "4") (pinfunction "X7_4") (pintype "bidirectional"))
    )
    (net (code "89") (name "unconnected-(IC13A-X6-Pad2)") (class "Default")
      (node (ref "IC13") (pin "2") (pinfunction "X6_2") (pintype "bidirectional"))
    )
    (net (code "90") (name "unconnected-(IC13A-X7-Pad4)") (class "Default")
      (node (ref "IC13") (pin "4") (pinfunction "X7_4") (pintype "bidirectional"))
    )
  )
)
